# ButtonAndSwitches.net
KiCad netlist of a schematic drawn in Altium Designer
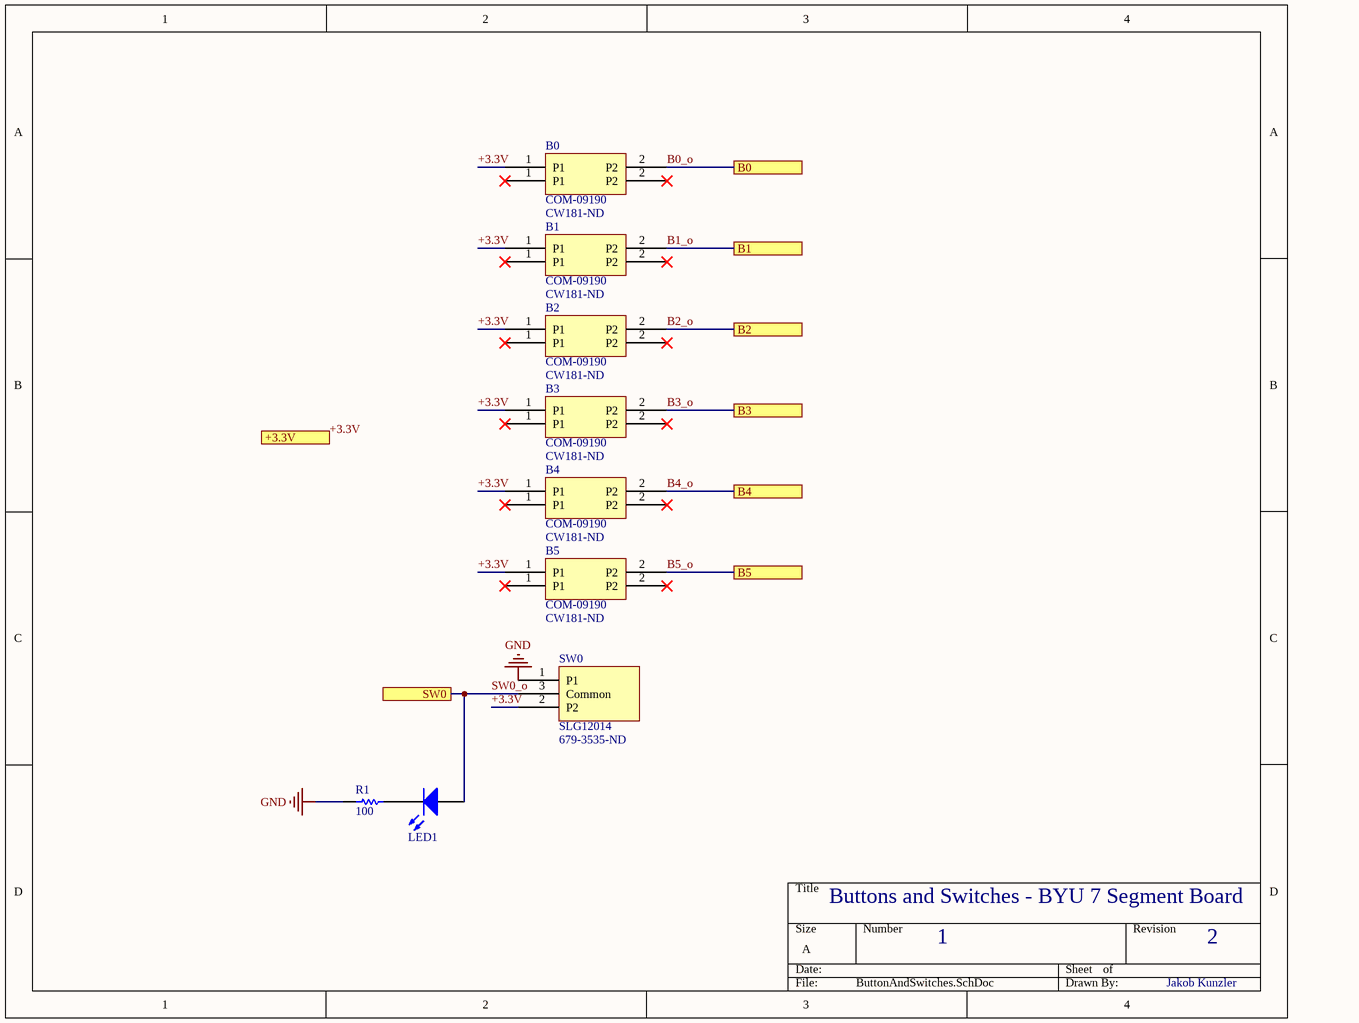
[diagram p0: ButtonAndSwitches.SchDoc]

(export (version "E")
  (design (tool "Eeschema 10.0.6"))
  (components
    (comp (ref "B0")
      (value "COM-09190")
      (footprint "COM-09190")
      (description "Momentary Pushbutton Switch - 12mm Square")
      (fields (field (name "SUPPLIER PART NUMBER 1") "CW181-ND"))
      (libsource (lib "BYU7SegBoard") (part "Push Button_Tactile"))
    )
    (comp (ref "B1")
      (value "COM-09190")
      (footprint "COM-09190")
      (description "Momentary Pushbutton Switch - 12mm Square")
      (fields (field (name "SUPPLIER PART NUMBER 1") "CW181-ND"))
      (libsource (lib "BYU7SegBoard") (part "Push Button_Tactile"))
    )
    (comp (ref "B2")
      (value "COM-09190")
      (footprint "COM-09190")
      (description "Momentary Pushbutton Switch - 12mm Square")
      (fields (field (name "SUPPLIER PART NUMBER 1") "CW181-ND"))
      (libsource (lib "BYU7SegBoard") (part "Push Button_Tactile"))
    )
    (comp (ref "B3")
      (value "COM-09190")
      (footprint "COM-09190")
      (description "Momentary Pushbutton Switch - 12mm Square")
      (fields (field (name "SUPPLIER PART NUMBER 1") "CW181-ND"))
      (libsource (lib "BYU7SegBoard") (part "Push Button_Tactile"))
    )
    (comp (ref "B4")
      (value "COM-09190")
      (footprint "COM-09190")
      (description "Momentary Pushbutton Switch - 12mm Square")
      (fields (field (name "SUPPLIER PART NUMBER 1") "CW181-ND"))
      (libsource (lib "BYU7SegBoard") (part "Push Button_Tactile"))
    )
    (comp (ref "B5")
      (value "COM-09190")
      (footprint "COM-09190")
      (description "Momentary Pushbutton Switch - 12mm Square")
      (fields (field (name "SUPPLIER PART NUMBER 1") "CW181-ND"))
      (libsource (lib "BYU7SegBoard") (part "Push Button_Tactile"))
    )
    (comp (ref "LED1")
      (value "LTL-4223")
      (footprint "LED Through")
      (description "2 V drop 10 mA Red")
      (libsource (lib "BYU7SegBoard") (part "LED_RED"))
    )
    (comp (ref "R1")
      (value "100")
      (footprint "Resistor Through Hole")
      (description "CF14JT100R")
      (libsource (lib "BYU7SegBoard") (part "Resistor_100"))
    )
    (comp (ref "SW0")
      (value "SLG12014")
      (footprint "SLG12014")
      (description "SWITCH SLIDE SPDT 300MA 125V")
      (fields (field (name "SUPPLIER PART NUMBER 1") "679-3535-ND"))
      (libsource (lib "BYU7SegBoard") (part "SlideSwitch"))
    )
  )
  (nets
    (net (code "1") (name "/+3.3V") (class "Default")
      (node (ref "B0") (pin "1") (pinfunction "P1_1") (pintype "passive"))
      (node (ref "B1") (pin "1") (pinfunction "P1_1") (pintype "passive"))
      (node (ref "B2") (pin "1") (pinfunction "P1_1") (pintype "passive"))
      (node (ref "B3") (pin "1") (pinfunction "P1_1") (pintype "passive"))
      (node (ref "B4") (pin "1") (pinfunction "P1_1") (pintype "passive"))
      (node (ref "B5") (pin "1") (pinfunction "P1_1") (pintype "passive"))
      (node (ref "SW0") (pin "2") (pinfunction "P2_2") (pintype "passive"))
    )
    (net (code "2") (name "/B0_o") (class "Default")
      (node (ref "B0") (pin "2") (pinfunction "P2_2") (pintype "passive"))
    )
    (net (code "3") (name "/B1_o") (class "Default")
      (node (ref "B1") (pin "2") (pinfunction "P2_2") (pintype "passive"))
    )
    (net (code "4") (name "/B2_o") (class "Default")
      (node (ref "B2") (pin "2") (pinfunction "P2_2") (pintype "passive"))
    )
    (net (code "5") (name "/B3_o") (class "Default")
      (node (ref "B3") (pin "2") (pinfunction "P2_2") (pintype "passive"))
    )
    (net (code "6") (name "/B4_o") (class "Default")
      (node (ref "B4") (pin "2") (pinfunction "P2_2") (pintype "passive"))
    )
    (net (code "7") (name "/B5_o") (class "Default")
      (node (ref "B5") (pin "2") (pinfunction "P2_2") (pintype "passive"))
    )
    (net (code "8") (name "/SW0_o") (class "Default")
      (node (ref "LED1") (pin "1") (pinfunction "A_1") (pintype "passive"))
      (node (ref "SW0") (pin "3") (pinfunction "Common_3") (pintype "passive"))
    )
    (net (code "9") (name "GND") (class "Default")
      (node (ref "R1") (pin "2") (pinfunction "2_2") (pintype "passive"))
      (node (ref "SW0") (pin "1") (pinfunction "P1_1") (pintype "passive"))
    )
    (net (code "10") (name "Net-(LED1-K)") (class "Default")
      (node (ref "LED1") (pin "2") (pinfunction "K_2") (pintype "passive"))
      (node (ref "R1") (pin "1") (pinfunction "1_1") (pintype "passive"))
    )
    (net (code "11") (name "unconnected-(B0-P1-Pad1)") (class "Default")
      (node (ref "B0") (pin "1") (pinfunction "P1_1") (pintype "passive+no_connect"))
    )
    (net (code "12") (name "unconnected-(B0-P2-Pad2)") (class "Default")
      (node (ref "B0") (pin "2") (pinfunction "P2_2") (pintype "passive+no_connect"))
    )
    (net (code "13") (name "unconnected-(B1-P1-Pad1)") (class "Default")
      (node (ref "B1") (pin "1") (pinfunction "P1_1") (pintype "passive+no_connect"))
    )
    (net (code "14") (name "unconnected-(B1-P2-Pad2)") (class "Default")
      (node (ref "B1") (pin "2") (pinfunction "P2_2") (pintype "passive+no_connect"))
    )
    (net (code "15") (name "unconnected-(B2-P1-Pad1)") (class "Default")
      (node (ref "B2") (pin "1") (pinfunction "P1_1") (pintype "passive+no_connect"))
    )
    (net (code "16") (name "unconnected-(B2-P2-Pad2)") (class "Default")
      (node (ref "B2") (pin "2") (pinfunction "P2_2") (pintype "passive+no_connect"))
    )
    (net (code "17") (name "unconnected-(B3-P1-Pad1)") (class "Default")
      (node (ref "B3") (pin "1") (pinfunction "P1_1") (pintype "passive+no_connect"))
    )
    (net (code "18") (name "unconnected-(B3-P2-Pad2)") (class "Default")
      (node (ref "B3") (pin "2") (pinfunction "P2_2") (pintype "passive+no_connect"))
    )
    (net (code "19") (name "unconnected-(B4-P1-Pad1)") (class "Default")
      (node (ref "B4") (pin "1") (pinfunction "P1_1") (pintype "passive+no_connect"))
    )
    (net (code "20") (name "unconnected-(B4-P2-Pad2)") (class "Default")
      (node (ref "B4") (pin "2") (pinfunction "P2_2") (pintype "passive+no_connect"))
    )
    (net (code "21") (name "unconnected-(B5-P1-Pad1)") (class "Default")
      (node (ref "B5") (pin "1") (pinfunction "P1_1") (pintype "passive+no_connect"))
    )
    (net (code "22") (name "unconnected-(B5-P2-Pad2)") (class "Default")
      (node (ref "B5") (pin "2") (pinfunction "P2_2") (pintype "passive+no_connect"))
    )
  )
)
